# BME280_Card.net
KiCad netlist of a schematic drawn in EAGLE
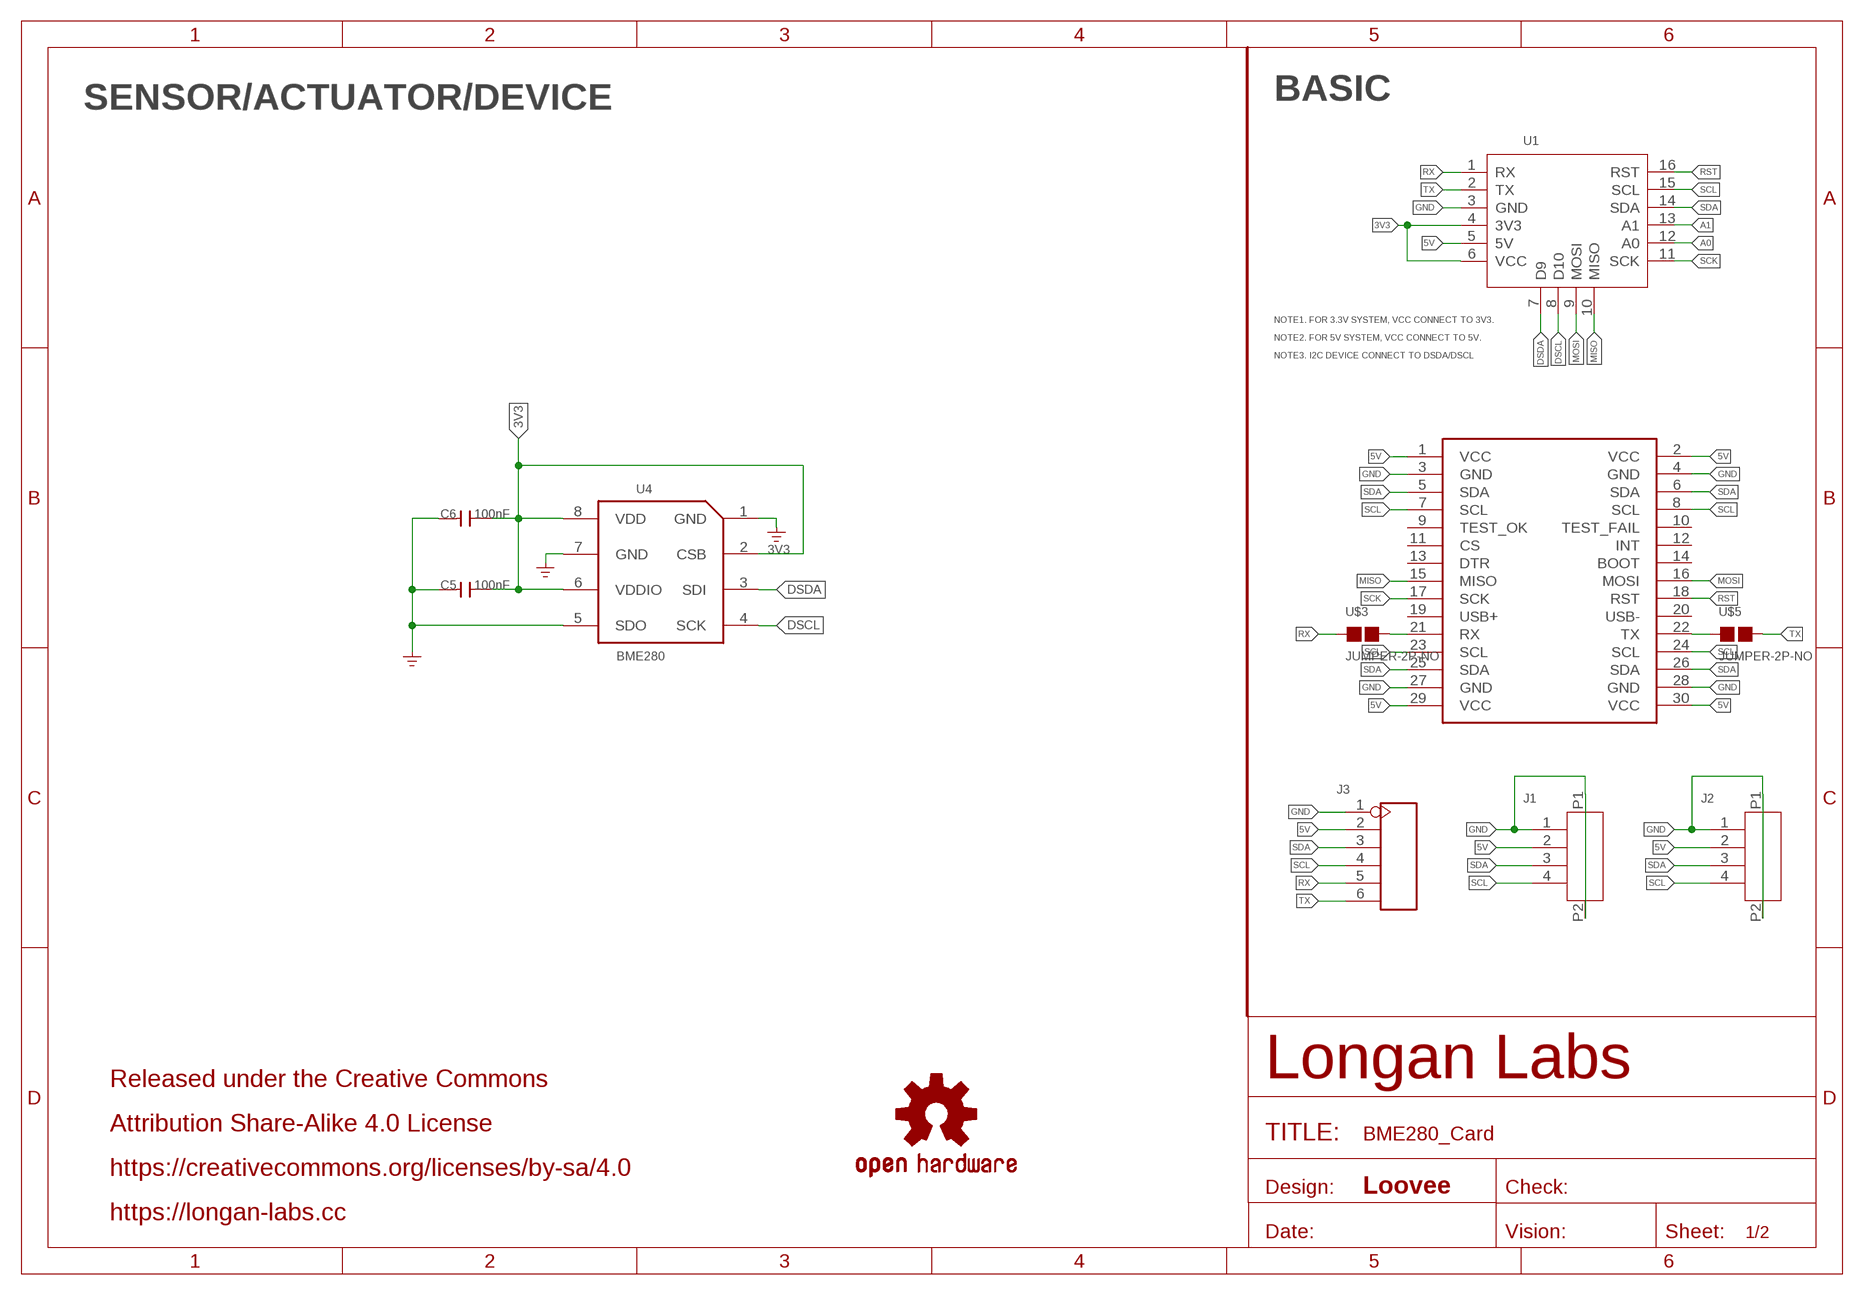
[diagram p0: schematic, sheet 1]

(export (version "E")
  (design (tool "Eeschema 10.0.6"))
  (components
    (comp (ref "C5")
      (value "100nF")
      (footprint "eagle-import:C0603")
      (libsource (lib "eagle-import") (part "CAP-0603"))
    )
    (comp (ref "C6")
      (value "100nF")
      (footprint "eagle-import:C0603")
      (libsource (lib "eagle-import") (part "CAP-0603"))
    )
    (comp (ref "J1")
      (value "HEADER-4P-1.0")
      (footprint "eagle-import:4P-1.0-90D")
      (libsource (lib "eagle-import") (part "HEADER-4P-1.0"))
    )
    (comp (ref "J2")
      (value "HEADER-4P-1.0")
      (footprint "eagle-import:4P-1.0-90D")
      (libsource (lib "eagle-import") (part "HEADER-4P-1.0"))
    )
    (comp (ref "J3")
      (value "HEADER-6P-55/35MIL")
      (footprint "eagle-import:H6-2.54")
      (libsource (lib "eagle-import") (part "HEADER-6P-55/35MIL"))
    )
    (comp (ref "LOGO2")
      (value "OSHW-LOGOS")
      (footprint "eagle-import:OSHW-LOGO-S")
      (libsource (lib "eagle-import") (part "OSHW-LOGOS"))
    )
    (comp (ref "MOUDLE1")
      (value "MOUDLE-2X15P-2.54'BOARD'")
      (footprint "eagle-import:MOUDLE-2X15P-2.54")
      (libsource (lib "eagle-import") (part "MOUDLE-2X15P-2.54'BOARD'"))
    )
    (comp (ref "U$3")
      (value "JUMPER-2P-NO")
      (footprint "eagle-import:2P-SMD-NO")
      (libsource (lib "eagle-import") (part "JUMPER-2P-NO"))
    )
    (comp (ref "U$5")
      (value "JUMPER-2P-NO")
      (footprint "eagle-import:2P-SMD-NO")
      (libsource (lib "eagle-import") (part "JUMPER-2P-NO"))
    )
    (comp (ref "U1")
      (value "MOUDLE-CARDS")
      (footprint "eagle-import:16P-2.0-CARDS")
      (libsource (lib "eagle-import") (part "MOUDLE-CARDS"))
    )
    (comp (ref "U4")
      (value "BME280")
      (footprint "eagle-import:LGA8-0.65-2.5X2.5X0.95MM")
      (fields (field (name "MPN") "BST-BME280"))
      (libsource (lib "eagle-import") (part "SENSOR-BME280"))
    )
  )
  (nets
    (net (code "1") (name "3V3") (class "Default")
      (node (ref "C5") (pin "1") (pinfunction "1_1") (pintype "passive"))
      (node (ref "C6") (pin "1") (pinfunction "1_1") (pintype "passive"))
      (node (ref "U1") (pin "4") (pinfunction "3V3_4") (pintype "bidirectional"))
      (node (ref "U1") (pin "6") (pinfunction "VCC_6") (pintype "bidirectional"))
      (node (ref "U4") (pin "2") (pinfunction "CSB_2") (pintype "bidirectional"))
      (node (ref "U4") (pin "6") (pinfunction "VDDIO_6") (pintype "power_in"))
      (node (ref "U4") (pin "8") (pinfunction "VDD_8") (pintype "power_in"))
    )
    (net (code "2") (name "5V") (class "Default")
      (node (ref "J1") (pin "2") (pinfunction "2_2") (pintype "bidirectional"))
      (node (ref "J2") (pin "2") (pinfunction "2_2") (pintype "bidirectional"))
      (node (ref "J3") (pin "2") (pinfunction "2_2") (pintype "bidirectional"))
      (node (ref "MOUDLE1") (pin "1") (pinfunction "VCC_1") (pintype "bidirectional"))
      (node (ref "MOUDLE1") (pin "2") (pinfunction "VCC_2") (pintype "bidirectional"))
      (node (ref "MOUDLE1") (pin "29") (pinfunction "VCC_29") (pintype "bidirectional"))
      (node (ref "MOUDLE1") (pin "30") (pinfunction "VCC_30") (pintype "bidirectional"))
      (node (ref "U1") (pin "5") (pinfunction "5V_5") (pintype "bidirectional"))
    )
    (net (code "3") (name "A0") (class "Default")
      (node (ref "U1") (pin "12") (pinfunction "A0_12") (pintype "bidirectional"))
    )
    (net (code "4") (name "A1") (class "Default")
      (node (ref "U1") (pin "13") (pinfunction "A1_13") (pintype "bidirectional"))
    )
    (net (code "5") (name "DSCL") (class "Default")
      (node (ref "U1") (pin "8") (pinfunction "D10_8") (pintype "bidirectional"))
      (node (ref "U4") (pin "4") (pinfunction "SCK_4") (pintype "bidirectional"))
    )
    (net (code "6") (name "DSDA") (class "Default")
      (node (ref "U1") (pin "7") (pinfunction "D9_7") (pintype "bidirectional"))
      (node (ref "U4") (pin "3") (pinfunction "SDI_3") (pintype "bidirectional"))
    )
    (net (code "7") (name "GND") (class "Default")
      (node (ref "C5") (pin "2") (pinfunction "2_2") (pintype "passive"))
      (node (ref "C6") (pin "2") (pinfunction "2_2") (pintype "passive"))
      (node (ref "J1") (pin "1") (pinfunction "1_1") (pintype "bidirectional"))
      (node (ref "J1") (pin "P1") (pinfunction "P1_P1") (pintype "bidirectional"))
      (node (ref "J1") (pin "P2") (pinfunction "P2_P2") (pintype "bidirectional"))
      (node (ref "J2") (pin "1") (pinfunction "1_1") (pintype "bidirectional"))
      (node (ref "J2") (pin "P1") (pinfunction "P1_P1") (pintype "bidirectional"))
      (node (ref "J2") (pin "P2") (pinfunction "P2_P2") (pintype "bidirectional"))
      (node (ref "J3") (pin "1") (pinfunction "1_1") (pintype "bidirectional"))
      (node (ref "MOUDLE1") (pin "27") (pinfunction "GND_27") (pintype "bidirectional"))
      (node (ref "MOUDLE1") (pin "28") (pinfunction "GND_28") (pintype "bidirectional"))
      (node (ref "MOUDLE1") (pin "3") (pinfunction "GND_3") (pintype "bidirectional"))
      (node (ref "MOUDLE1") (pin "4") (pinfunction "GND_4") (pintype "bidirectional"))
      (node (ref "U1") (pin "3") (pinfunction "GND_3") (pintype "bidirectional"))
      (node (ref "U4") (pin "1") (pinfunction "GND_1") (pintype "power_in"))
      (node (ref "U4") (pin "5") (pinfunction "SDO_5") (pintype "bidirectional"))
      (node (ref "U4") (pin "7") (pinfunction "GND_7") (pintype "power_in"))
    )
    (net (code "8") (name "MISO") (class "Default")
      (node (ref "MOUDLE1") (pin "15") (pinfunction "MISO_15") (pintype "bidirectional"))
      (node (ref "U1") (pin "10") (pinfunction "MISO_10") (pintype "bidirectional"))
    )
    (net (code "9") (name "MOSI") (class "Default")
      (node (ref "MOUDLE1") (pin "16") (pinfunction "MOSI_16") (pintype "bidirectional"))
      (node (ref "U1") (pin "9") (pinfunction "MOSI_9") (pintype "bidirectional"))
    )
    (net (code "10") (name "Net-(MOUDLE1-RX)") (class "Default")
      (node (ref "MOUDLE1") (pin "21") (pinfunction "RX_21") (pintype "bidirectional"))
      (node (ref "U$3") (pin "2") (pinfunction "2_2") (pintype "bidirectional"))
    )
    (net (code "11") (name "Net-(MOUDLE1-TX)") (class "Default")
      (node (ref "MOUDLE1") (pin "22") (pinfunction "TX_22") (pintype "bidirectional"))
      (node (ref "U$5") (pin "1") (pinfunction "1_1") (pintype "bidirectional"))
    )
    (net (code "12") (name "RST") (class "Default")
      (node (ref "MOUDLE1") (pin "18") (pinfunction "RST_18") (pintype "bidirectional"))
      (node (ref "U1") (pin "16") (pinfunction "RST_16") (pintype "bidirectional"))
    )
    (net (code "13") (name "RX") (class "Default")
      (node (ref "J3") (pin "5") (pinfunction "5_5") (pintype "bidirectional"))
      (node (ref "U$3") (pin "1") (pinfunction "1_1") (pintype "bidirectional"))
      (node (ref "U1") (pin "1") (pinfunction "RX_1") (pintype "bidirectional"))
    )
    (net (code "14") (name "SCK") (class "Default")
      (node (ref "MOUDLE1") (pin "17") (pinfunction "SCK_17") (pintype "bidirectional"))
      (node (ref "U1") (pin "11") (pinfunction "SCK_11") (pintype "bidirectional"))
    )
    (net (code "15") (name "SCL") (class "Default")
      (node (ref "J1") (pin "4") (pinfunction "4_4") (pintype "bidirectional"))
      (node (ref "J2") (pin "4") (pinfunction "4_4") (pintype "bidirectional"))
      (node (ref "J3") (pin "4") (pinfunction "4_4") (pintype "bidirectional"))
      (node (ref "MOUDLE1") (pin "23") (pinfunction "SCL_23") (pintype "bidirectional"))
      (node (ref "MOUDLE1") (pin "24") (pinfunction "SCL_24") (pintype "bidirectional"))
      (node (ref "MOUDLE1") (pin "7") (pinfunction "SCL_7") (pintype "bidirectional"))
      (node (ref "MOUDLE1") (pin "8") (pinfunction "SCL_8") (pintype "bidirectional"))
      (node (ref "U1") (pin "15") (pinfunction "SCL_15") (pintype "bidirectional"))
    )
    (net (code "16") (name "SDA") (class "Default")
      (node (ref "J1") (pin "3") (pinfunction "3_3") (pintype "bidirectional"))
      (node (ref "J2") (pin "3") (pinfunction "3_3") (pintype "bidirectional"))
      (node (ref "J3") (pin "3") (pinfunction "3_3") (pintype "bidirectional"))
      (node (ref "MOUDLE1") (pin "25") (pinfunction "SDA_25") (pintype "bidirectional"))
      (node (ref "MOUDLE1") (pin "26") (pinfunction "SDA_26") (pintype "bidirectional"))
      (node (ref "MOUDLE1") (pin "5") (pinfunction "SDA_5") (pintype "bidirectional"))
      (node (ref "MOUDLE1") (pin "6") (pinfunction "SDA_6") (pintype "bidirectional"))
      (node (ref "U1") (pin "14") (pinfunction "SDA_14") (pintype "bidirectional"))
    )
    (net (code "17") (name "TX") (class "Default")
      (node (ref "J3") (pin "6") (pinfunction "6_6") (pintype "bidirectional"))
      (node (ref "U$5") (pin "2") (pinfunction "2_2") (pintype "bidirectional"))
      (node (ref "U1") (pin "2") (pinfunction "TX_2") (pintype "bidirectional"))
    )
    (net (code "18") (name "unconnected-(MOUDLE1-BOOT-Pad14)") (class "Default")
      (node (ref "MOUDLE1") (pin "14") (pinfunction "BOOT_14") (pintype "bidirectional"))
    )
    (net (code "19") (name "unconnected-(MOUDLE1-CS-Pad11)") (class "Default")
      (node (ref "MOUDLE1") (pin "11") (pinfunction "CS_11") (pintype "bidirectional"))
    )
    (net (code "20") (name "unconnected-(MOUDLE1-DTR-Pad13)") (class "Default")
      (node (ref "MOUDLE1") (pin "13") (pinfunction "DTR_13") (pintype "bidirectional"))
    )
    (net (code "21") (name "unconnected-(MOUDLE1-INT-Pad12)") (class "Default")
      (node (ref "MOUDLE1") (pin "12") (pinfunction "INT_12") (pintype "bidirectional"))
    )
    (net (code "22") (name "unconnected-(MOUDLE1-TEST_FAIL-Pad10)") (class "Default")
      (node (ref "MOUDLE1") (pin "10") (pinfunction "TEST_FAIL_10") (pintype "bidirectional"))
    )
    (net (code "23") (name "unconnected-(MOUDLE1-TEST_OK-Pad9)") (class "Default")
      (node (ref "MOUDLE1") (pin "9") (pinfunction "TEST_OK_9") (pintype "bidirectional"))
    )
    (net (code "24") (name "unconnected-(MOUDLE1-USB+-Pad19)") (class "Default")
      (node (ref "MOUDLE1") (pin "19") (pinfunction "USB+_19") (pintype "bidirectional"))
    )
    (net (code "25") (name "unconnected-(MOUDLE1-USB--Pad20)") (class "Default")
      (node (ref "MOUDLE1") (pin "20") (pinfunction "USB-_20") (pintype "bidirectional"))
    )
  )
)
